# Switch_Board_v1_FIN.net
KiCad netlist of a schematic drawn in EAGLE
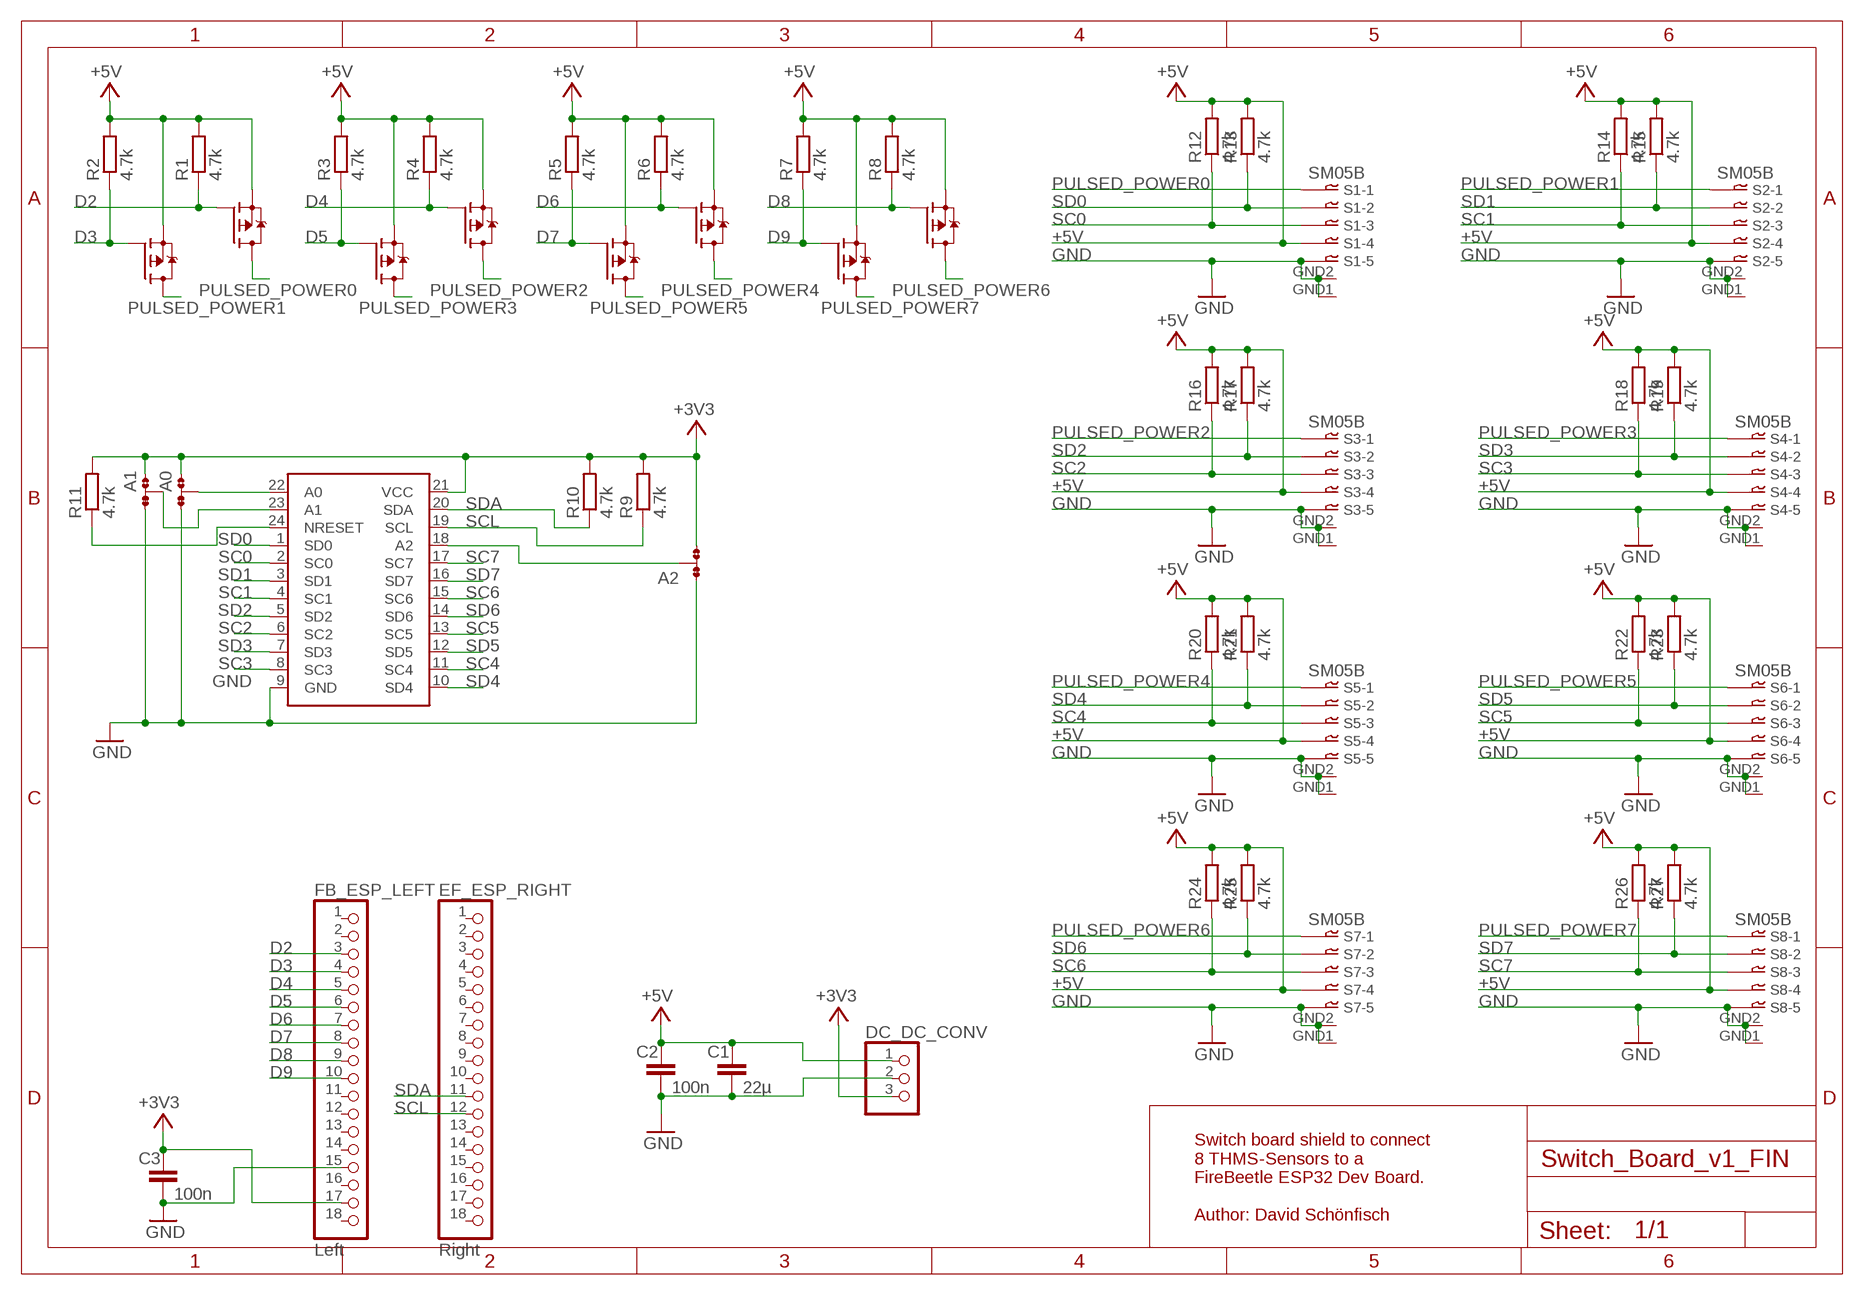
[diagram p0: schematic, sheet 1]

(export (version "E")
  (design (tool "Eeschema 10.0.6"))
  (components
    (comp (ref "A0")
      (value "0R-JUMP-1CON")
      (footprint "eagle-import:D0R-JMP(D)")
      (libsource (lib "eagle-import") (part "0R-JUMP-1CON"))
    )
    (comp (ref "A1")
      (value "0R-JUMP-1CON")
      (footprint "eagle-import:D0R-JMP(D)")
      (libsource (lib "eagle-import") (part "0R-JUMP-1CON"))
    )
    (comp (ref "A2")
      (value "0R-JUMP-1CON")
      (footprint "eagle-import:D0R-JMP(D)")
      (libsource (lib "eagle-import") (part "0R-JUMP-1CON"))
    )
    (comp (ref "C1")
      (value "22µ")
      (footprint "eagle-import:C0603")
      (libsource (lib "eagle-import") (part "C-EUC0603"))
    )
    (comp (ref "C2")
      (value "100n")
      (footprint "eagle-import:C0603")
      (libsource (lib "eagle-import") (part "C-EUC0603"))
    )
    (comp (ref "C3")
      (value "100n")
      (footprint "eagle-import:C0603")
      (libsource (lib "eagle-import") (part "C-EUC0603"))
    )
    (comp (ref "DC_DC_CONV")
      (value "0")
      (footprint "eagle-import:1X03")
      (libsource (lib "eagle-import") (part "PINHD-1X3"))
    )
    (comp (ref "EF_ESP_RIGHT")
      (value "Right")
      (footprint "eagle-import:1X18")
      (libsource (lib "eagle-import") (part "PINHD-1X18"))
    )
    (comp (ref "FB_ESP_LEFT")
      (value "Left")
      (footprint "eagle-import:1X18")
      (libsource (lib "eagle-import") (part "PINHD-1X18"))
    )
    (comp (ref "R1")
      (value "4.7k")
      (footprint "eagle-import:R0603")
      (libsource (lib "eagle-import") (part "R-EU_R0603"))
    )
    (comp (ref "R2")
      (value "4.7k")
      (footprint "eagle-import:R0603")
      (libsource (lib "eagle-import") (part "R-EU_R0603"))
    )
    (comp (ref "R3")
      (value "4.7k")
      (footprint "eagle-import:R0603")
      (libsource (lib "eagle-import") (part "R-EU_R0603"))
    )
    (comp (ref "R4")
      (value "4.7k")
      (footprint "eagle-import:R0603")
      (libsource (lib "eagle-import") (part "R-EU_R0603"))
    )
    (comp (ref "R5")
      (value "4.7k")
      (footprint "eagle-import:R0603")
      (libsource (lib "eagle-import") (part "R-EU_R0603"))
    )
    (comp (ref "R6")
      (value "4.7k")
      (footprint "eagle-import:R0603")
      (libsource (lib "eagle-import") (part "R-EU_R0603"))
    )
    (comp (ref "R7")
      (value "4.7k")
      (footprint "eagle-import:R0603")
      (libsource (lib "eagle-import") (part "R-EU_R0603"))
    )
    (comp (ref "R8")
      (value "4.7k")
      (footprint "eagle-import:R0603")
      (libsource (lib "eagle-import") (part "R-EU_R0603"))
    )
    (comp (ref "R9")
      (value "4.7k")
      (footprint "eagle-import:R0603")
      (libsource (lib "eagle-import") (part "R-EU_R0603"))
    )
    (comp (ref "R10")
      (value "4.7k")
      (footprint "eagle-import:R0603")
      (libsource (lib "eagle-import") (part "R-EU_R0603"))
    )
    (comp (ref "R11")
      (value "4.7k")
      (footprint "eagle-import:R0603")
      (libsource (lib "eagle-import") (part "R-EU_R0603"))
    )
    (comp (ref "R12")
      (value "4.7k")
      (footprint "eagle-import:R0603")
      (libsource (lib "eagle-import") (part "R-EU_R0603"))
    )
    (comp (ref "R13")
      (value "4.7k")
      (footprint "eagle-import:R0603")
      (libsource (lib "eagle-import") (part "R-EU_R0603"))
    )
    (comp (ref "R14")
      (value "4.7k")
      (footprint "eagle-import:R0603")
      (libsource (lib "eagle-import") (part "R-EU_R0603"))
    )
    (comp (ref "R15")
      (value "4.7k")
      (footprint "eagle-import:R0603")
      (libsource (lib "eagle-import") (part "R-EU_R0603"))
    )
    (comp (ref "R16")
      (value "4.7k")
      (footprint "eagle-import:R0603")
      (libsource (lib "eagle-import") (part "R-EU_R0603"))
    )
    (comp (ref "R17")
      (value "4.7k")
      (footprint "eagle-import:R0603")
      (libsource (lib "eagle-import") (part "R-EU_R0603"))
    )
    (comp (ref "R18")
      (value "4.7k")
      (footprint "eagle-import:R0603")
      (libsource (lib "eagle-import") (part "R-EU_R0603"))
    )
    (comp (ref "R19")
      (value "4.7k")
      (footprint "eagle-import:R0603")
      (libsource (lib "eagle-import") (part "R-EU_R0603"))
    )
    (comp (ref "R20")
      (value "4.7k")
      (footprint "eagle-import:R0603")
      (libsource (lib "eagle-import") (part "R-EU_R0603"))
    )
    (comp (ref "R21")
      (value "4.7k")
      (footprint "eagle-import:R0603")
      (libsource (lib "eagle-import") (part "R-EU_R0603"))
    )
    (comp (ref "R22")
      (value "4.7k")
      (footprint "eagle-import:R0603")
      (libsource (lib "eagle-import") (part "R-EU_R0603"))
    )
    (comp (ref "R23")
      (value "4.7k")
      (footprint "eagle-import:R0603")
      (libsource (lib "eagle-import") (part "R-EU_R0603"))
    )
    (comp (ref "R24")
      (value "4.7k")
      (footprint "eagle-import:R0603")
      (libsource (lib "eagle-import") (part "R-EU_R0603"))
    )
    (comp (ref "R25")
      (value "4.7k")
      (footprint "eagle-import:R0603")
      (libsource (lib "eagle-import") (part "R-EU_R0603"))
    )
    (comp (ref "R26")
      (value "4.7k")
      (footprint "eagle-import:R0603")
      (libsource (lib "eagle-import") (part "R-EU_R0603"))
    )
    (comp (ref "R27")
      (value "4.7k")
      (footprint "eagle-import:R0603")
      (libsource (lib "eagle-import") (part "R-EU_R0603"))
    )
    (comp (ref "S1")
      (value "SM05B")
      (footprint "eagle-import:SM05B")
      (libsource (lib "eagle-import") (part "SM05B"))
    )
    (comp (ref "S2")
      (value "SM05B")
      (footprint "eagle-import:SM05B")
      (libsource (lib "eagle-import") (part "SM05B"))
    )
    (comp (ref "S3")
      (value "SM05B")
      (footprint "eagle-import:SM05B")
      (libsource (lib "eagle-import") (part "SM05B"))
    )
    (comp (ref "S4")
      (value "SM05B")
      (footprint "eagle-import:SM05B")
      (libsource (lib "eagle-import") (part "SM05B"))
    )
    (comp (ref "S5")
      (value "SM05B")
      (footprint "eagle-import:SM05B")
      (libsource (lib "eagle-import") (part "SM05B"))
    )
    (comp (ref "S6")
      (value "SM05B")
      (footprint "eagle-import:SM05B")
      (libsource (lib "eagle-import") (part "SM05B"))
    )
    (comp (ref "S7")
      (value "SM05B")
      (footprint "eagle-import:SM05B")
      (libsource (lib "eagle-import") (part "SM05B"))
    )
    (comp (ref "S8")
      (value "SM05B")
      (footprint "eagle-import:SM05B")
      (libsource (lib "eagle-import") (part "SM05B"))
    )
    (comp (ref "U$1")
      (value "TCA9548PVQFN")
      (footprint "eagle-import:S-PVQFN-N24")
      (libsource (lib "eagle-import") (part "TCA9548PVQFN"))
    )
    (comp (ref "U$2")
      (value "UM6J1N")
      (footprint "eagle-import:SOT363_INFINEON")
      (libsource (lib "eagle-import") (part "UM6J1N"))
    )
    (comp (ref "U$3")
      (value "UM6J1N")
      (footprint "eagle-import:SOT363_INFINEON")
      (libsource (lib "eagle-import") (part "UM6J1N"))
    )
    (comp (ref "U$4")
      (value "UM6J1N")
      (footprint "eagle-import:SOT363_INFINEON")
      (libsource (lib "eagle-import") (part "UM6J1N"))
    )
    (comp (ref "U$5")
      (value "UM6J1N")
      (footprint "eagle-import:SOT363_INFINEON")
      (libsource (lib "eagle-import") (part "UM6J1N"))
    )
  )
  (nets
    (net (code "1") (name "+3V3") (class "Default")
      (node (ref "A0") (pin "1") (pinfunction "1_1") (pintype "passive"))
      (node (ref "A1") (pin "1") (pinfunction "1_1") (pintype "passive"))
      (node (ref "A2") (pin "1") (pinfunction "1_1") (pintype "passive"))
      (node (ref "C3") (pin "1") (pinfunction "1_1") (pintype "passive"))
      (node (ref "DC_DC_CONV") (pin "3") (pinfunction "3_3") (pintype "passive"))
      (node (ref "FB_ESP_LEFT") (pin "17") (pinfunction "17_17") (pintype "passive"))
      (node (ref "R10") (pin "2") (pinfunction "2_2") (pintype "passive"))
      (node (ref "R11") (pin "2") (pinfunction "2_2") (pintype "passive"))
      (node (ref "R9") (pin "2") (pinfunction "2_2") (pintype "passive"))
      (node (ref "U$1") (pin "21") (pinfunction "VCC_21") (pintype "bidirectional"))
    )
    (net (code "2") (name "+5V") (class "Default")
      (node (ref "C1") (pin "1") (pinfunction "1_1") (pintype "passive"))
      (node (ref "C2") (pin "1") (pinfunction "1_1") (pintype "passive"))
      (node (ref "DC_DC_CONV") (pin "1") (pinfunction "1_1") (pintype "passive"))
      (node (ref "R1") (pin "2") (pinfunction "2_2") (pintype "passive"))
      (node (ref "R12") (pin "2") (pinfunction "2_2") (pintype "passive"))
      (node (ref "R13") (pin "2") (pinfunction "2_2") (pintype "passive"))
      (node (ref "R14") (pin "2") (pinfunction "2_2") (pintype "passive"))
      (node (ref "R15") (pin "2") (pinfunction "2_2") (pintype "passive"))
      (node (ref "R16") (pin "2") (pinfunction "2_2") (pintype "passive"))
      (node (ref "R17") (pin "2") (pinfunction "2_2") (pintype "passive"))
      (node (ref "R18") (pin "2") (pinfunction "2_2") (pintype "passive"))
      (node (ref "R19") (pin "2") (pinfunction "2_2") (pintype "passive"))
      (node (ref "R2") (pin "2") (pinfunction "2_2") (pintype "passive"))
      (node (ref "R20") (pin "2") (pinfunction "2_2") (pintype "passive"))
      (node (ref "R21") (pin "2") (pinfunction "2_2") (pintype "passive"))
      (node (ref "R22") (pin "2") (pinfunction "2_2") (pintype "passive"))
      (node (ref "R23") (pin "2") (pinfunction "2_2") (pintype "passive"))
      (node (ref "R24") (pin "2") (pinfunction "2_2") (pintype "passive"))
      (node (ref "R25") (pin "2") (pinfunction "2_2") (pintype "passive"))
      (node (ref "R26") (pin "2") (pinfunction "2_2") (pintype "passive"))
      (node (ref "R27") (pin "2") (pinfunction "2_2") (pintype "passive"))
      (node (ref "R3") (pin "2") (pinfunction "2_2") (pintype "passive"))
      (node (ref "R4") (pin "2") (pinfunction "2_2") (pintype "passive"))
      (node (ref "R5") (pin "2") (pinfunction "2_2") (pintype "passive"))
      (node (ref "R6") (pin "2") (pinfunction "2_2") (pintype "passive"))
      (node (ref "R7") (pin "2") (pinfunction "2_2") (pintype "passive"))
      (node (ref "R8") (pin "2") (pinfunction "2_2") (pintype "passive"))
      (node (ref "S1") (pin "4") (pinfunction "1_4") (pintype "passive"))
      (node (ref "S2") (pin "4") (pinfunction "1_4") (pintype "passive"))
      (node (ref "S3") (pin "4") (pinfunction "1_4") (pintype "passive"))
      (node (ref "S4") (pin "4") (pinfunction "1_4") (pintype "passive"))
      (node (ref "S5") (pin "4") (pinfunction "1_4") (pintype "passive"))
      (node (ref "S6") (pin "4") (pinfunction "1_4") (pintype "passive"))
      (node (ref "S7") (pin "4") (pinfunction "1_4") (pintype "passive"))
      (node (ref "S8") (pin "4") (pinfunction "1_4") (pintype "passive"))
      (node (ref "U$2") (pin "1") (pinfunction "S_1") (pintype "passive"))
      (node (ref "U$2") (pin "4") (pinfunction "S_4") (pintype "passive"))
      (node (ref "U$3") (pin "1") (pinfunction "S_1") (pintype "passive"))
      (node (ref "U$3") (pin "4") (pinfunction "S_4") (pintype "passive"))
      (node (ref "U$4") (pin "1") (pinfunction "S_1") (pintype "passive"))
      (node (ref "U$4") (pin "4") (pinfunction "S_4") (pintype "passive"))
      (node (ref "U$5") (pin "1") (pinfunction "S_1") (pintype "passive"))
      (node (ref "U$5") (pin "4") (pinfunction "S_4") (pintype "passive"))
    )
    (net (code "3") (name "/D2") (class "Default")
      (node (ref "FB_ESP_LEFT") (pin "3") (pinfunction "3_3") (pintype "passive"))
      (node (ref "R1") (pin "1") (pinfunction "1_1") (pintype "passive"))
      (node (ref "U$2") (pin "2") (pinfunction "G_2") (pintype "passive"))
    )
    (net (code "4") (name "/D3") (class "Default")
      (node (ref "FB_ESP_LEFT") (pin "4") (pinfunction "4_4") (pintype "passive"))
      (node (ref "R2") (pin "1") (pinfunction "1_1") (pintype "passive"))
      (node (ref "U$2") (pin "5") (pinfunction "G_5") (pintype "passive"))
    )
    (net (code "5") (name "/D4") (class "Default")
      (node (ref "FB_ESP_LEFT") (pin "5") (pinfunction "5_5") (pintype "passive"))
      (node (ref "R4") (pin "1") (pinfunction "1_1") (pintype "passive"))
      (node (ref "U$3") (pin "2") (pinfunction "G_2") (pintype "passive"))
    )
    (net (code "6") (name "/D5") (class "Default")
      (node (ref "FB_ESP_LEFT") (pin "6") (pinfunction "6_6") (pintype "passive"))
      (node (ref "R3") (pin "1") (pinfunction "1_1") (pintype "passive"))
      (node (ref "U$3") (pin "5") (pinfunction "G_5") (pintype "passive"))
    )
    (net (code "7") (name "/D6") (class "Default")
      (node (ref "FB_ESP_LEFT") (pin "7") (pinfunction "7_7") (pintype "passive"))
      (node (ref "R6") (pin "1") (pinfunction "1_1") (pintype "passive"))
      (node (ref "U$4") (pin "2") (pinfunction "G_2") (pintype "passive"))
    )
    (net (code "8") (name "/D7") (class "Default")
      (node (ref "FB_ESP_LEFT") (pin "8") (pinfunction "8_8") (pintype "passive"))
      (node (ref "R5") (pin "1") (pinfunction "1_1") (pintype "passive"))
      (node (ref "U$4") (pin "5") (pinfunction "G_5") (pintype "passive"))
    )
    (net (code "9") (name "/D8") (class "Default")
      (node (ref "FB_ESP_LEFT") (pin "9") (pinfunction "9_9") (pintype "passive"))
      (node (ref "R8") (pin "1") (pinfunction "1_1") (pintype "passive"))
      (node (ref "U$5") (pin "2") (pinfunction "G_2") (pintype "passive"))
    )
    (net (code "10") (name "/D9") (class "Default")
      (node (ref "FB_ESP_LEFT") (pin "10") (pinfunction "10_10") (pintype "passive"))
      (node (ref "R7") (pin "1") (pinfunction "1_1") (pintype "passive"))
      (node (ref "U$5") (pin "5") (pinfunction "G_5") (pintype "passive"))
    )
    (net (code "11") (name "/PULSED_POWER0") (class "Default")
      (node (ref "S1") (pin "1") (pinfunction "1_1") (pintype "passive"))
      (node (ref "U$2") (pin "6") (pinfunction "D_6") (pintype "passive"))
    )
    (net (code "12") (name "/PULSED_POWER1") (class "Default")
      (node (ref "S2") (pin "1") (pinfunction "1_1") (pintype "passive"))
      (node (ref "U$2") (pin "3") (pinfunction "D_3") (pintype "passive"))
    )
    (net (code "13") (name "/PULSED_POWER2") (class "Default")
      (node (ref "S3") (pin "1") (pinfunction "1_1") (pintype "passive"))
      (node (ref "U$3") (pin "6") (pinfunction "D_6") (pintype "passive"))
    )
    (net (code "14") (name "/PULSED_POWER3") (class "Default")
      (node (ref "S4") (pin "1") (pinfunction "1_1") (pintype "passive"))
      (node (ref "U$3") (pin "3") (pinfunction "D_3") (pintype "passive"))
    )
    (net (code "15") (name "/PULSED_POWER4") (class "Default")
      (node (ref "S5") (pin "1") (pinfunction "1_1") (pintype "passive"))
      (node (ref "U$4") (pin "6") (pinfunction "D_6") (pintype "passive"))
    )
    (net (code "16") (name "/PULSED_POWER5") (class "Default")
      (node (ref "S6") (pin "1") (pinfunction "1_1") (pintype "passive"))
      (node (ref "U$4") (pin "3") (pinfunction "D_3") (pintype "passive"))
    )
    (net (code "17") (name "/PULSED_POWER6") (class "Default")
      (node (ref "S7") (pin "1") (pinfunction "1_1") (pintype "passive"))
      (node (ref "U$5") (pin "6") (pinfunction "D_6") (pintype "passive"))
    )
    (net (code "18") (name "/PULSED_POWER7") (class "Default")
      (node (ref "S8") (pin "1") (pinfunction "1_1") (pintype "passive"))
      (node (ref "U$5") (pin "3") (pinfunction "D_3") (pintype "passive"))
    )
    (net (code "19") (name "/SC0") (class "Default")
      (node (ref "R12") (pin "1") (pinfunction "1_1") (pintype "passive"))
      (node (ref "S1") (pin "3") (pinfunction "1_3") (pintype "passive"))
      (node (ref "U$1") (pin "2") (pinfunction "SC0_2") (pintype "bidirectional"))
    )
    (net (code "20") (name "/SC1") (class "Default")
      (node (ref "R14") (pin "1") (pinfunction "1_1") (pintype "passive"))
      (node (ref "S2") (pin "3") (pinfunction "1_3") (pintype "passive"))
      (node (ref "U$1") (pin "4") (pinfunction "SC1_4") (pintype "bidirectional"))
    )
    (net (code "21") (name "/SC2") (class "Default")
      (node (ref "R16") (pin "1") (pinfunction "1_1") (pintype "passive"))
      (node (ref "S3") (pin "3") (pinfunction "1_3") (pintype "passive"))
      (node (ref "U$1") (pin "6") (pinfunction "SC2_6") (pintype "bidirectional"))
    )
    (net (code "22") (name "/SC3") (class "Default")
      (node (ref "R18") (pin "1") (pinfunction "1_1") (pintype "passive"))
      (node (ref "S4") (pin "3") (pinfunction "1_3") (pintype "passive"))
      (node (ref "U$1") (pin "8") (pinfunction "SC3_8") (pintype "bidirectional"))
    )
    (net (code "23") (name "/SC4") (class "Default")
      (node (ref "R20") (pin "1") (pinfunction "1_1") (pintype "passive"))
      (node (ref "S5") (pin "3") (pinfunction "1_3") (pintype "passive"))
      (node (ref "U$1") (pin "11") (pinfunction "SC4_11") (pintype "bidirectional"))
    )
    (net (code "24") (name "/SC5") (class "Default")
      (node (ref "R22") (pin "1") (pinfunction "1_1") (pintype "passive"))
      (node (ref "S6") (pin "3") (pinfunction "1_3") (pintype "passive"))
      (node (ref "U$1") (pin "13") (pinfunction "SC5_13") (pintype "bidirectional"))
    )
    (net (code "25") (name "/SC6") (class "Default")
      (node (ref "R24") (pin "1") (pinfunction "1_1") (pintype "passive"))
      (node (ref "S7") (pin "3") (pinfunction "1_3") (pintype "passive"))
      (node (ref "U$1") (pin "15") (pinfunction "SC6_15") (pintype "bidirectional"))
    )
    (net (code "26") (name "/SC7") (class "Default")
      (node (ref "R26") (pin "1") (pinfunction "1_1") (pintype "passive"))
      (node (ref "S8") (pin "3") (pinfunction "1_3") (pintype "passive"))
      (node (ref "U$1") (pin "17") (pinfunction "SC7_17") (pintype "bidirectional"))
    )
    (net (code "27") (name "/SCL") (class "Default")
      (node (ref "EF_ESP_RIGHT") (pin "12") (pinfunction "12_12") (pintype "passive"))
      (node (ref "R9") (pin "1") (pinfunction "1_1") (pintype "passive"))
      (node (ref "U$1") (pin "19") (pinfunction "SCL_19") (pintype "bidirectional"))
    )
    (net (code "28") (name "/SD0") (class "Default")
      (node (ref "R13") (pin "1") (pinfunction "1_1") (pintype "passive"))
      (node (ref "S1") (pin "2") (pinfunction "1_2") (pintype "passive"))
      (node (ref "U$1") (pin "1") (pinfunction "SD0_1") (pintype "bidirectional"))
    )
    (net (code "29") (name "/SD1") (class "Default")
      (node (ref "R15") (pin "1") (pinfunction "1_1") (pintype "passive"))
      (node (ref "S2") (pin "2") (pinfunction "1_2") (pintype "passive"))
      (node (ref "U$1") (pin "3") (pinfunction "SD1_3") (pintype "bidirectional"))
    )
    (net (code "30") (name "/SD2") (class "Default")
      (node (ref "R17") (pin "1") (pinfunction "1_1") (pintype "passive"))
      (node (ref "S3") (pin "2") (pinfunction "1_2") (pintype "passive"))
      (node (ref "U$1") (pin "5") (pinfunction "SD2_5") (pintype "bidirectional"))
    )
    (net (code "31") (name "/SD3") (class "Default")
      (node (ref "R19") (pin "1") (pinfunction "1_1") (pintype "passive"))
      (node (ref "S4") (pin "2") (pinfunction "1_2") (pintype "passive"))
      (node (ref "U$1") (pin "7") (pinfunction "SD3_7") (pintype "bidirectional"))
    )
    (net (code "32") (name "/SD4") (class "Default")
      (node (ref "R21") (pin "1") (pinfunction "1_1") (pintype "passive"))
      (node (ref "S5") (pin "2") (pinfunction "1_2") (pintype "passive"))
      (node (ref "U$1") (pin "10") (pinfunction "SD4_10") (pintype "bidirectional"))
    )
    (net (code "33") (name "/SD5") (class "Default")
      (node (ref "R23") (pin "1") (pinfunction "1_1") (pintype "passive"))
      (node (ref "S6") (pin "2") (pinfunction "1_2") (pintype "passive"))
      (node (ref "U$1") (pin "12") (pinfunction "SD5_12") (pintype "bidirectional"))
    )
    (net (code "34") (name "/SD6") (class "Default")
      (node (ref "R25") (pin "1") (pinfunction "1_1") (pintype "passive"))
      (node (ref "S7") (pin "2") (pinfunction "1_2") (pintype "passive"))
      (node (ref "U$1") (pin "14") (pinfunction "SD6_14") (pintype "bidirectional"))
    )
    (net (code "35") (name "/SD7") (class "Default")
      (node (ref "R27") (pin "1") (pinfunction "1_1") (pintype "passive"))
      (node (ref "S8") (pin "2") (pinfunction "1_2") (pintype "passive"))
      (node (ref "U$1") (pin "16") (pinfunction "SD7_16") (pintype "bidirectional"))
    )
    (net (code "36") (name "/SDA") (class "Default")
      (node (ref "EF_ESP_RIGHT") (pin "11") (pinfunction "11_11") (pintype "passive"))
      (node (ref "R10") (pin "1") (pinfunction "1_1") (pintype "passive"))
      (node (ref "U$1") (pin "20") (pinfunction "SDA_20") (pintype "bidirectional"))
    )
    (net (code "37") (name "GND") (class "Default")
      (node (ref "A0") (pin "3") (pinfunction "3_3") (pintype "passive"))
      (node (ref "A1") (pin "3") (pinfunction "3_3") (pintype "passive"))
      (node (ref "A2") (pin "3") (pinfunction "3_3") (pintype "passive"))
      (node (ref "C1") (pin "2") (pinfunction "2_2") (pintype "passive"))
      (node (ref "C2") (pin "2") (pinfunction "2_2") (pintype "passive"))
      (node (ref "C3") (pin "2") (pinfunction "2_2") (pintype "passive"))
      (node (ref "DC_DC_CONV") (pin "2") (pinfunction "2_2") (pintype "passive"))
      (node (ref "FB_ESP_LEFT") (pin "15") (pinfunction "15_15") (pintype "passive"))
      (node (ref "S1") (pin "5") (pinfunction "1_5") (pintype "passive"))
      (node (ref "S1") (pin "GND1") (pinfunction "P$1_GND1") (pintype "power_in"))
      (node (ref "S1") (pin "GND2") (pinfunction "P$1_GND2") (pintype "power_in"))
      (node (ref "S2") (pin "5") (pinfunction "1_5") (pintype "passive"))
      (node (ref "S2") (pin "GND1") (pinfunction "P$1_GND1") (pintype "power_in"))
      (node (ref "S2") (pin "GND2") (pinfunction "P$1_GND2") (pintype "power_in"))
      (node (ref "S3") (pin "5") (pinfunction "1_5") (pintype "passive"))
      (node (ref "S3") (pin "GND1") (pinfunction "P$1_GND1") (pintype "power_in"))
      (node (ref "S3") (pin "GND2") (pinfunction "P$1_GND2") (pintype "power_in"))
      (node (ref "S4") (pin "5") (pinfunction "1_5") (pintype "passive"))
      (node (ref "S4") (pin "GND1") (pinfunction "P$1_GND1") (pintype "power_in"))
      (node (ref "S4") (pin "GND2") (pinfunction "P$1_GND2") (pintype "power_in"))
      (node (ref "S5") (pin "5") (pinfunction "1_5") (pintype "passive"))
      (node (ref "S5") (pin "GND1") (pinfunction "P$1_GND1") (pintype "power_in"))
      (node (ref "S5") (pin "GND2") (pinfunction "P$1_GND2") (pintype "power_in"))
      (node (ref "S6") (pin "5") (pinfunction "1_5") (pintype "passive"))
      (node (ref "S6") (pin "GND1") (pinfunction "P$1_GND1") (pintype "power_in"))
      (node (ref "S6") (pin "GND2") (pinfunction "P$1_GND2") (pintype "power_in"))
      (node (ref "S7") (pin "5") (pinfunction "1_5") (pintype "passive"))
      (node (ref "S7") (pin "GND1") (pinfunction "P$1_GND1") (pintype "power_in"))
      (node (ref "S7") (pin "GND2") (pinfunction "P$1_GND2") (pintype "power_in"))
      (node (ref "S8") (pin "5") (pinfunction "1_5") (pintype "passive"))
      (node (ref "S8") (pin "GND1") (pinfunction "P$1_GND1") (pintype "power_in"))
      (node (ref "S8") (pin "GND2") (pinfunction "P$1_GND2") (pintype "power_in"))
      (node (ref "U$1") (pin "9") (pinfunction "GND_9") (pintype "bidirectional"))
    )
    (net (code "38") (name "Net-(U$1-A0)") (class "Default")
      (node (ref "A0") (pin "2") (pinfunction "2_2") (pintype "passive"))
      (node (ref "U$1") (pin "22") (pinfunction "A0_22") (pintype "bidirectional"))
    )
    (net (code "39") (name "Net-(U$1-A1)") (class "Default")
      (node (ref "A1") (pin "2") (pinfunction "2_2") (pintype "passive"))
      (node (ref "U$1") (pin "23") (pinfunction "A1_23") (pintype "bidirectional"))
    )
    (net (code "40") (name "Net-(U$1-A2)") (class "Default")
      (node (ref "A2") (pin "2") (pinfunction "2_2") (pintype "passive"))
      (node (ref "U$1") (pin "18") (pinfunction "A2_18") (pintype "bidirectional"))
    )
    (net (code "41") (name "Net-(U$1-NRESET)") (class "Default")
      (node (ref "R11") (pin "1") (pinfunction "1_1") (pintype "passive"))
      (node (ref "U$1") (pin "24") (pinfunction "NRESET_24") (pintype "bidirectional"))
    )
    (net (code "42") (name "unconnected-(EF_ESP_RIGHT-Pad1)") (class "Default")
      (node (ref "EF_ESP_RIGHT") (pin "1") (pinfunction "1_1") (pintype "passive"))
    )
    (net (code "43") (name "unconnected-(EF_ESP_RIGHT-Pad2)") (class "Default")
      (node (ref "EF_ESP_RIGHT") (pin "2") (pinfunction "2_2") (pintype "passive"))
    )
    (net (code "44") (name "unconnected-(EF_ESP_RIGHT-Pad3)") (class "Default")
      (node (ref "EF_ESP_RIGHT") (pin "3") (pinfunction "3_3") (pintype "passive"))
    )
    (net (code "45") (name "unconnected-(EF_ESP_RIGHT-Pad4)") (class "Default")
      (node (ref "EF_ESP_RIGHT") (pin "4") (pinfunction "4_4") (pintype "passive"))
    )
    (net (code "46") (name "unconnected-(EF_ESP_RIGHT-Pad5)") (class "Default")
      (node (ref "EF_ESP_RIGHT") (pin "5") (pinfunction "5_5") (pintype "passive"))
    )
    (net (code "47") (name "unconnected-(EF_ESP_RIGHT-Pad6)") (class "Default")
      (node (ref "EF_ESP_RIGHT") (pin "6") (pinfunction "6_6") (pintype "passive"))
    )
    (net (code "48") (name "unconnected-(EF_ESP_RIGHT-Pad7)") (class "Default")
      (node (ref "EF_ESP_RIGHT") (pin "7") (pinfunction "7_7") (pintype "passive"))
    )
    (net (code "49") (name "unconnected-(EF_ESP_RIGHT-Pad8)") (class "Default")
      (node (ref "EF_ESP_RIGHT") (pin "8") (pinfunction "8_8") (pintype "passive"))
    )
    (net (code "50") (name "unconnected-(EF_ESP_RIGHT-Pad9)") (class "Default")
      (node (ref "EF_ESP_RIGHT") (pin "9") (pinfunction "9_9") (pintype "passive"))
    )
    (net (code "51") (name "unconnected-(EF_ESP_RIGHT-Pad10)") (class "Default")
      (node (ref "EF_ESP_RIGHT") (pin "10") (pinfunction "10_10") (pintype "passive"))
    )
    (net (code "52") (name "unconnected-(EF_ESP_RIGHT-Pad13)") (class "Default")
      (node (ref "EF_ESP_RIGHT") (pin "13") (pinfunction "13_13") (pintype "passive"))
    )
    (net (code "53") (name "unconnected-(EF_ESP_RIGHT-Pad14)") (class "Default")
      (node (ref "EF_ESP_RIGHT") (pin "14") (pinfunction "14_14") (pintype "passive"))
    )
    (net (code "54") (name "unconnected-(EF_ESP_RIGHT-Pad15)") (class "Default")
      (node (ref "EF_ESP_RIGHT") (pin "15") (pinfunction "15_15") (pintype "passive"))
    )
    (net (code "55") (name "unconnected-(EF_ESP_RIGHT-Pad16)") (class "Default")
      (node (ref "EF_ESP_RIGHT") (pin "16") (pinfunction "16_16") (pintype "passive"))
    )
    (net (code "56") (name "unconnected-(EF_ESP_RIGHT-Pad17)") (class "Default")
      (node (ref "EF_ESP_RIGHT") (pin "17") (pinfunction "17_17") (pintype "passive"))
    )
    (net (code "57") (name "unconnected-(EF_ESP_RIGHT-Pad18)") (class "Default")
      (node (ref "EF_ESP_RIGHT") (pin "18") (pinfunction "18_18") (pintype "passive"))
    )
    (net (code "58") (name "unconnected-(FB_ESP_LEFT-Pad1)") (class "Default")
      (node (ref "FB_ESP_LEFT") (pin "1") (pinfunction "1_1") (pintype "passive"))
    )
    (net (code "59") (name "unconnected-(FB_ESP_LEFT-Pad2)") (class "Default")
      (node (ref "FB_ESP_LEFT") (pin "2") (pinfunction "2_2") (pintype "passive"))
    )
    (net (code "60") (name "unconnected-(FB_ESP_LEFT-Pad11)") (class "Default")
      (node (ref "FB_ESP_LEFT") (pin "11") (pinfunction "11_11") (pintype "passive"))
    )
    (net (code "61") (name "unconnected-(FB_ESP_LEFT-Pad12)") (class "Default")
      (node (ref "FB_ESP_LEFT") (pin "12") (pinfunction "12_12") (pintype "passive"))
    )
    (net (code "62") (name "unconnected-(FB_ESP_LEFT-Pad13)") (class "Default")
      (node (ref "FB_ESP_LEFT") (pin "13") (pinfunction "13_13") (pintype "passive"))
    )
    (net (code "63") (name "unconnected-(FB_ESP_LEFT-Pad14)") (class "Default")
      (node (ref "FB_ESP_LEFT") (pin "14") (pinfunction "14_14") (pintype "passive"))
    )
    (net (code "64") (name "unconnected-(FB_ESP_LEFT-Pad16)") (class "Default")
      (node (ref "FB_ESP_LEFT") (pin "16") (pinfunction "16_16") (pintype "passive"))
    )
    (net (code "65") (name "unconnected-(FB_ESP_LEFT-Pad18)") (class "Default")
      (node (ref "FB_ESP_LEFT") (pin "18") (pinfunction "18_18") (pintype "passive"))
    )
  )
)
